# Jlink_OB.net
KiCad netlist of a schematic drawn in Altium Designer
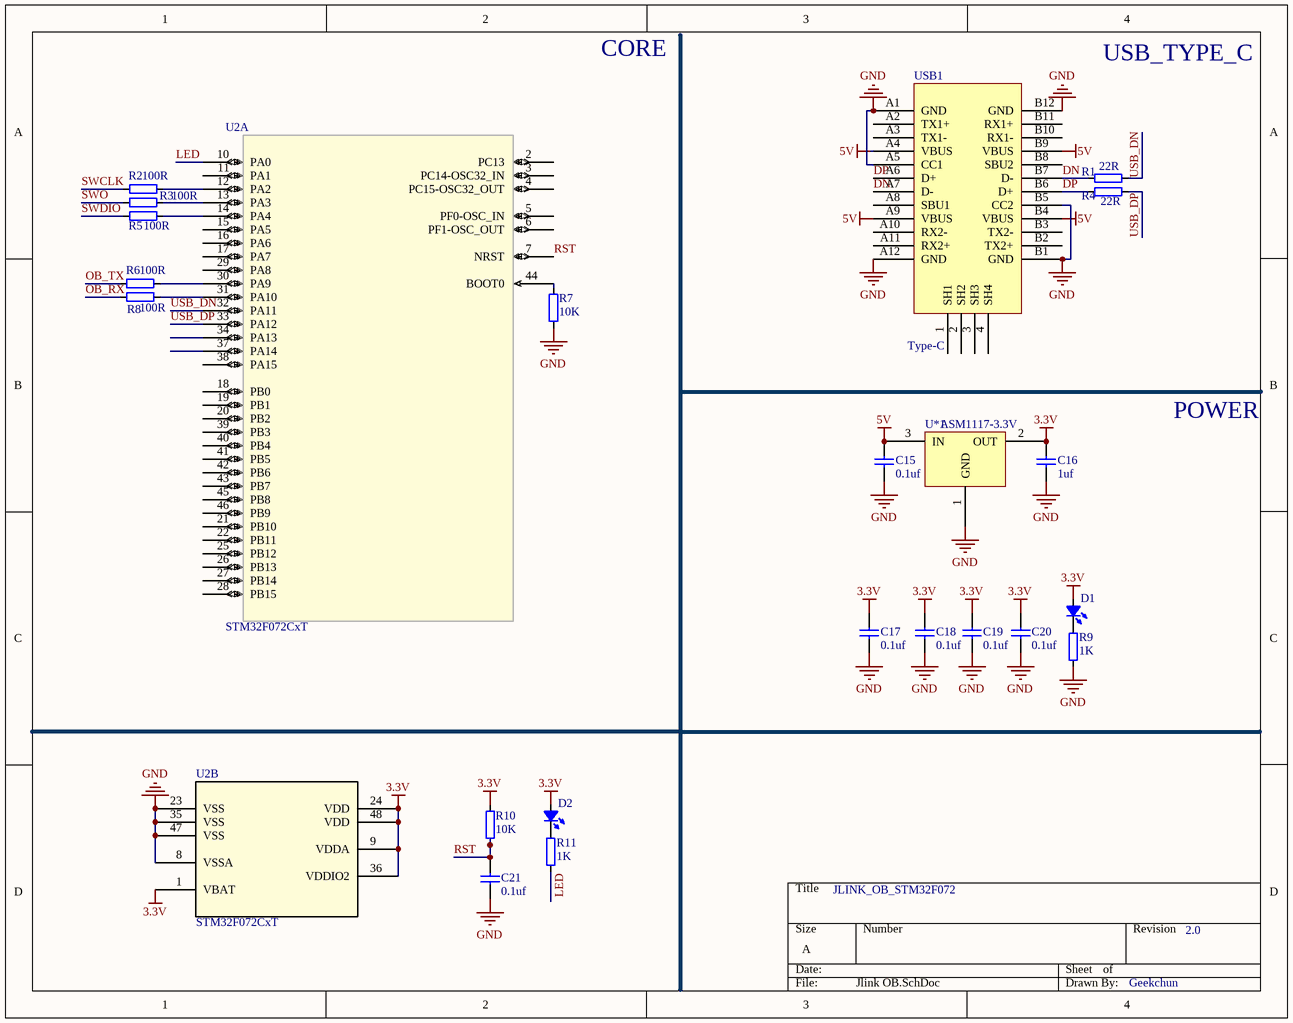
[diagram p0: Jlink OB.SchDoc]

(export (version "E")
  (design (tool "Eeschema 10.0.6"))
  (components
    (comp (ref "C15")
      (value "0.1uf")
      (footprint "C 0603_L")
      (description "Capacitor, NP0, ?.1pF")
      (fields (field (name "PART NUMBER") "C0402-1.2p") (field (name "PUBLISHER") "Nordic Semiconductor"))
      (libsource (lib "52") (part "CAP"))
    )
    (comp (ref "C16")
      (value "1uf")
      (footprint "C 0603_L")
      (description "Capacitor, NP0, ?.1pF")
      (fields (field (name "PART NUMBER") "C0402-1.2p") (field (name "PUBLISHER") "Nordic Semiconductor"))
      (libsource (lib "52") (part "CAP"))
    )
    (comp (ref "C17")
      (value "0.1uf")
      (footprint "C 0603_L")
      (description "Capacitor, NP0, ?.1pF")
      (fields (field (name "PART NUMBER") "C0402-1.2p") (field (name "PUBLISHER") "Nordic Semiconductor"))
      (libsource (lib "52") (part "CAP"))
    )
    (comp (ref "C18")
      (value "0.1uf")
      (footprint "C 0603_L")
      (description "Capacitor, NP0, ?.1pF")
      (fields (field (name "PART NUMBER") "C0402-1.2p") (field (name "PUBLISHER") "Nordic Semiconductor"))
      (libsource (lib "52") (part "CAP"))
    )
    (comp (ref "C19")
      (value "0.1uf")
      (footprint "C 0603_L")
      (description "Capacitor, NP0, ?.1pF")
      (fields (field (name "PART NUMBER") "C0402-1.2p") (field (name "PUBLISHER") "Nordic Semiconductor"))
      (libsource (lib "52") (part "CAP"))
    )
    (comp (ref "C20")
      (value "0.1uf")
      (footprint "C 0603_L")
      (description "Capacitor, NP0, ?.1pF")
      (fields (field (name "PART NUMBER") "C0402-1.2p") (field (name "PUBLISHER") "Nordic Semiconductor"))
      (libsource (lib "52") (part "CAP"))
    )
    (comp (ref "C21")
      (value "0.1uf")
      (footprint "C 0603_L")
      (description "Capacitor, NP0, ?.1pF")
      (fields (field (name "PART NUMBER") "C0402-1.2p") (field (name "PUBLISHER") "Nordic Semiconductor"))
      (libsource (lib "52") (part "CAP"))
    )
    (comp (ref "D1")
      (value "LED_0603")
      (footprint "LED_0603_BLUE")
      (description "LED")
      (libsource (lib "SCH_Active") (part "LED_0603"))
    )
    (comp (ref "D2")
      (value "LED_0603")
      (footprint "LED_0603_GREEN")
      (description "LED")
      (libsource (lib "SCH_Active") (part "LED_0603"))
    )
    (comp (ref "R1") (value "22R") (footprint "R 0603_L") (libsource (lib "电阻") (part "RES")))
    (comp (ref "R2") (value "100R") (footprint "R 0603_L") (libsource (lib "电阻") (part "RES")))
    (comp (ref "R3") (value "100R") (footprint "R 0603_L") (libsource (lib "电阻") (part "RES")))
    (comp (ref "R4") (value "22R") (footprint "R 0603_L") (libsource (lib "电阻") (part "RES")))
    (comp (ref "R5") (value "100R") (footprint "R 0603_L") (libsource (lib "电阻") (part "RES")))
    (comp (ref "R6") (value "100R") (footprint "R 0603_L") (libsource (lib "电阻") (part "RES")))
    (comp (ref "R7") (value "10K") (footprint "R 0603_L") (libsource (lib "电阻") (part "RES")))
    (comp (ref "R8") (value "100R") (footprint "R 0603_L") (libsource (lib "电阻") (part "RES")))
    (comp (ref "R9") (value "1K") (footprint "R 0603_L") (libsource (lib "电阻") (part "RES")))
    (comp (ref "R10") (value "10K") (footprint "R 0603_L") (libsource (lib "电阻") (part "RES")))
    (comp (ref "R11") (value "1K") (footprint "R 0603_L") (libsource (lib "电阻") (part "RES")))
    (comp (ref "U*1")
      (value "ASM1117-3.3V")
      (footprint "SOT-89")
      (description "三端可调或固定电压3.3V")
      (libsource (lib "STM32F103C及ASM1117") (part "ASM1117-3.3V"))
    )
    (comp (ref "U2")
      (value "STM32F072CxT")
      (footprint "LQFP_P0.5_48")
      (description "Imported")
      (fields
        (field (name "MANUFACTURER_PART_NUMBER") "stm32f072cxt")
        (field (name "COPYRIGHT") "Copyright (C) 2016 Accelerated Designs. All rights reserved")
      )
      (libsource (lib "STM32F072CB") (part "STM32F072CxT"))
    )
    (comp (ref "USB1") (value "Type-C") (footprint "PCBComponent_1") (libsource (lib "元件") (part "Type-C")))
  )
  (nets
    (net (code "1") (name "/DN") (class "Default")
      (node (ref "R1") (pin "1") (pinfunction "1_1") (pintype "passive"))
      (node (ref "USB1") (pin "A7") (pinfunction "D-_A7") (pintype "passive"))
      (node (ref "USB1") (pin "B7") (pinfunction "D-_B7") (pintype "passive"))
    )
    (net (code "2") (name "/DP") (class "Default")
      (node (ref "R4") (pin "1") (pinfunction "1_1") (pintype "passive"))
      (node (ref "USB1") (pin "A6") (pinfunction "D+_A6") (pintype "passive"))
      (node (ref "USB1") (pin "B6") (pinfunction "D+_B6") (pintype "passive"))
    )
    (net (code "3") (name "/LED") (class "Default")
      (node (ref "R11") (pin "1") (pinfunction "1_1") (pintype "passive"))
      (node (ref "U2") (pin "10") (pinfunction "PA0_10") (pintype "bidirectional"))
    )
    (net (code "4") (name "/OB_RX") (class "Default")
      (node (ref "R8") (pin "1") (pinfunction "1_1") (pintype "passive"))
    )
    (net (code "5") (name "/OB_TX") (class "Default")
      (node (ref "R6") (pin "1") (pinfunction "1_1") (pintype "passive"))
    )
    (net (code "6") (name "/RST") (class "Default")
      (node (ref "C21") (pin "2") (pinfunction "2_2") (pintype "passive"))
      (node (ref "R10") (pin "1") (pinfunction "1_1") (pintype "passive"))
      (node (ref "U2") (pin "7") (pinfunction "NRST_7") (pintype "bidirectional"))
    )
    (net (code "7") (name "/SWCLK") (class "Default")
      (node (ref "R2") (pin "1") (pinfunction "1_1") (pintype "passive"))
    )
    (net (code "8") (name "/SWDIO") (class "Default")
      (node (ref "R5") (pin "1") (pinfunction "1_1") (pintype "passive"))
    )
    (net (code "9") (name "/SWO") (class "Default")
      (node (ref "R3") (pin "1") (pinfunction "1_1") (pintype "passive"))
    )
    (net (code "10") (name "/USB_DN") (class "Default")
      (node (ref "R1") (pin "2") (pinfunction "2_2") (pintype "passive"))
      (node (ref "U2") (pin "32") (pinfunction "PA11_32") (pintype "bidirectional"))
    )
    (net (code "11") (name "/USB_DP") (class "Default")
      (node (ref "R4") (pin "2") (pinfunction "2_2") (pintype "passive"))
      (node (ref "U2") (pin "33") (pinfunction "PA12_33") (pintype "bidirectional"))
    )
    (net (code "12") (name "3.3V") (class "Default")
      (node (ref "C16") (pin "2") (pinfunction "2_2") (pintype "passive"))
      (node (ref "C17") (pin "2") (pinfunction "2_2") (pintype "passive"))
      (node (ref "C18") (pin "2") (pinfunction "2_2") (pintype "passive"))
      (node (ref "C19") (pin "2") (pinfunction "2_2") (pintype "passive"))
      (node (ref "C20") (pin "2") (pinfunction "2_2") (pintype "passive"))
      (node (ref "D1") (pin "1") (pinfunction "A_1") (pintype "passive"))
      (node (ref "D2") (pin "1") (pinfunction "A_1") (pintype "passive"))
      (node (ref "R10") (pin "2") (pinfunction "2_2") (pintype "passive"))
      (node (ref "U*1") (pin "2") (pinfunction "OUT_2") (pintype "passive"))
      (node (ref "U2") (pin "1") (pinfunction "VBAT_1") (pintype "power_in"))
      (node (ref "U2") (pin "24") (pinfunction "VDD_24") (pintype "power_in"))
      (node (ref "U2") (pin "36") (pinfunction "VDDIO2_36") (pintype "power_in"))
      (node (ref "U2") (pin "48") (pinfunction "VDD_48") (pintype "power_in"))
      (node (ref "U2") (pin "9") (pinfunction "VDDA_9") (pintype "power_in"))
    )
    (net (code "13") (name "5V") (class "Default")
      (node (ref "C15") (pin "2") (pinfunction "2_2") (pintype "passive"))
      (node (ref "U*1") (pin "3") (pinfunction "IN_3") (pintype "passive"))
      (node (ref "USB1") (pin "A4") (pinfunction "VBUS_A4") (pintype "passive"))
      (node (ref "USB1") (pin "A9") (pinfunction "VBUS_A9") (pintype "passive"))
      (node (ref "USB1") (pin "B4") (pinfunction "VBUS_B4") (pintype "passive"))
      (node (ref "USB1") (pin "B9") (pinfunction "VBUS_B9") (pintype "passive"))
    )
    (net (code "14") (name "GND") (class "Default")
      (node (ref "C15") (pin "1") (pinfunction "1_1") (pintype "passive"))
      (node (ref "C16") (pin "1") (pinfunction "1_1") (pintype "passive"))
      (node (ref "C17") (pin "1") (pinfunction "1_1") (pintype "passive"))
      (node (ref "C18") (pin "1") (pinfunction "1_1") (pintype "passive"))
      (node (ref "C19") (pin "1") (pinfunction "1_1") (pintype "passive"))
      (node (ref "C20") (pin "1") (pinfunction "1_1") (pintype "passive"))
      (node (ref "C21") (pin "1") (pinfunction "1_1") (pintype "passive"))
      (node (ref "R7") (pin "2") (pinfunction "2_2") (pintype "passive"))
      (node (ref "R9") (pin "1") (pinfunction "1_1") (pintype "passive"))
      (node (ref "U*1") (pin "1") (pinfunction "GND_1") (pintype "passive"))
      (node (ref "U2") (pin "23") (pinfunction "VSS_23") (pintype "power_in"))
      (node (ref "U2") (pin "35") (pinfunction "VSS_35") (pintype "power_in"))
      (node (ref "U2") (pin "47") (pinfunction "VSS_47") (pintype "power_in"))
      (node (ref "U2") (pin "8") (pinfunction "VSSA_8") (pintype "power_in"))
      (node (ref "USB1") (pin "A1") (pinfunction "GND_A1") (pintype "passive"))
      (node (ref "USB1") (pin "A12") (pinfunction "GND_A12") (pintype "passive"))
      (node (ref "USB1") (pin "A5") (pinfunction "CC1_A5") (pintype "passive"))
      (node (ref "USB1") (pin "B1") (pinfunction "GND_B1") (pintype "passive"))
      (node (ref "USB1") (pin "B12") (pinfunction "GND_B12") (pintype "passive"))
      (node (ref "USB1") (pin "B5") (pinfunction "CC2_B5") (pintype "passive"))
    )
    (net (code "15") (name "Net-(D1-K)") (class "Default")
      (node (ref "D1") (pin "2") (pinfunction "K_2") (pintype "passive"))
      (node (ref "R9") (pin "2") (pinfunction "2_2") (pintype "passive"))
    )
    (net (code "16") (name "Net-(D2-K)") (class "Default")
      (node (ref "D2") (pin "2") (pinfunction "K_2") (pintype "passive"))
      (node (ref "R11") (pin "2") (pinfunction "2_2") (pintype "passive"))
    )
    (net (code "17") (name "Net-(U2A-BOOT0)") (class "Default")
      (node (ref "R7") (pin "1") (pinfunction "1_1") (pintype "passive"))
      (node (ref "U2") (pin "44") (pinfunction "BOOT0_44") (pintype "input"))
    )
    (net (code "18") (name "Net-(U2A-PA2)") (class "Default")
      (node (ref "R2") (pin "2") (pinfunction "2_2") (pintype "passive"))
      (node (ref "U2") (pin "12") (pinfunction "PA2_12") (pintype "bidirectional"))
    )
    (net (code "19") (name "Net-(U2A-PA3)") (class "Default")
      (node (ref "R3") (pin "2") (pinfunction "2_2") (pintype "passive"))
      (node (ref "U2") (pin "13") (pinfunction "PA3_13") (pintype "bidirectional"))
    )
    (net (code "20") (name "Net-(U2A-PA4)") (class "Default")
      (node (ref "R5") (pin "2") (pinfunction "2_2") (pintype "passive"))
      (node (ref "U2") (pin "14") (pinfunction "PA4_14") (pintype "bidirectional"))
    )
    (net (code "21") (name "Net-(U2A-PA9)") (class "Default")
      (node (ref "R6") (pin "2") (pinfunction "2_2") (pintype "passive"))
      (node (ref "U2") (pin "30") (pinfunction "PA9_30") (pintype "bidirectional"))
    )
    (net (code "22") (name "Net-(U2A-PA10)") (class "Default")
      (node (ref "R8") (pin "2") (pinfunction "2_2") (pintype "passive"))
      (node (ref "U2") (pin "31") (pinfunction "PA10_31") (pintype "bidirectional"))
    )
    (net (code "23") (name "unconnected-(U2A-PA1-Pad11)") (class "Default")
      (node (ref "U2") (pin "11") (pinfunction "PA1_11") (pintype "bidirectional"))
    )
    (net (code "24") (name "unconnected-(U2A-PA5-Pad15)") (class "Default")
      (node (ref "U2") (pin "15") (pinfunction "PA5_15") (pintype "bidirectional"))
    )
    (net (code "25") (name "unconnected-(U2A-PA6-Pad16)") (class "Default")
      (node (ref "U2") (pin "16") (pinfunction "PA6_16") (pintype "bidirectional"))
    )
    (net (code "26") (name "unconnected-(U2A-PA7-Pad17)") (class "Default")
      (node (ref "U2") (pin "17") (pinfunction "PA7_17") (pintype "bidirectional"))
    )
    (net (code "27") (name "unconnected-(U2A-PA8-Pad29)") (class "Default")
      (node (ref "U2") (pin "29") (pinfunction "PA8_29") (pintype "bidirectional"))
    )
    (net (code "28") (name "unconnected-(U2A-PA13-Pad34)") (class "Default")
      (node (ref "U2") (pin "34") (pinfunction "PA13_34") (pintype "bidirectional"))
    )
    (net (code "29") (name "unconnected-(U2A-PA14-Pad37)") (class "Default")
      (node (ref "U2") (pin "37") (pinfunction "PA14_37") (pintype "bidirectional"))
    )
    (net (code "30") (name "unconnected-(U2A-PA15-Pad38)") (class "Default")
      (node (ref "U2") (pin "38") (pinfunction "PA15_38") (pintype "bidirectional"))
    )
    (net (code "31") (name "unconnected-(U2A-PB0-Pad18)") (class "Default")
      (node (ref "U2") (pin "18") (pinfunction "PB0_18") (pintype "bidirectional"))
    )
    (net (code "32") (name "unconnected-(U2A-PB1-Pad19)") (class "Default")
      (node (ref "U2") (pin "19") (pinfunction "PB1_19") (pintype "bidirectional"))
    )
    (net (code "33") (name "unconnected-(U2A-PB2-Pad20)") (class "Default")
      (node (ref "U2") (pin "20") (pinfunction "PB2_20") (pintype "bidirectional"))
    )
    (net (code "34") (name "unconnected-(U2A-PB3-Pad39)") (class "Default")
      (node (ref "U2") (pin "39") (pinfunction "PB3_39") (pintype "bidirectional"))
    )
    (net (code "35") (name "unconnected-(U2A-PB4-Pad40)") (class "Default")
      (node (ref "U2") (pin "40") (pinfunction "PB4_40") (pintype "bidirectional"))
    )
    (net (code "36") (name "unconnected-(U2A-PB5-Pad41)") (class "Default")
      (node (ref "U2") (pin "41") (pinfunction "PB5_41") (pintype "bidirectional"))
    )
    (net (code "37") (name "unconnected-(U2A-PB6-Pad42)") (class "Default")
      (node (ref "U2") (pin "42") (pinfunction "PB6_42") (pintype "bidirectional"))
    )
    (net (code "38") (name "unconnected-(U2A-PB7-Pad43)") (class "Default")
      (node (ref "U2") (pin "43") (pinfunction "PB7_43") (pintype "bidirectional"))
    )
    (net (code "39") (name "unconnected-(U2A-PB8-Pad45)") (class "Default")
      (node (ref "U2") (pin "45") (pinfunction "PB8_45") (pintype "bidirectional"))
    )
    (net (code "40") (name "unconnected-(U2A-PB9-Pad46)") (class "Default")
      (node (ref "U2") (pin "46") (pinfunction "PB9_46") (pintype "bidirectional"))
    )
    (net (code "41") (name "unconnected-(U2A-PB10-Pad21)") (class "Default")
      (node (ref "U2") (pin "21") (pinfunction "PB10_21") (pintype "bidirectional"))
    )
    (net (code "42") (name "unconnected-(U2A-PB11-Pad22)") (class "Default")
      (node (ref "U2") (pin "22") (pinfunction "PB11_22") (pintype "bidirectional"))
    )
    (net (code "43") (name "unconnected-(U2A-PB12-Pad25)") (class "Default")
      (node (ref "U2") (pin "25") (pinfunction "PB12_25") (pintype "bidirectional"))
    )
    (net (code "44") (name "unconnected-(U2A-PB13-Pad26)") (class "Default")
      (node (ref "U2") (pin "26") (pinfunction "PB13_26") (pintype "bidirectional"))
    )
    (net (code "45") (name "unconnected-(U2A-PB14-Pad27)") (class "Default")
      (node (ref "U2") (pin "27") (pinfunction "PB14_27") (pintype "bidirectional"))
    )
    (net (code "46") (name "unconnected-(U2A-PB15-Pad28)") (class "Default")
      (node (ref "U2") (pin "28") (pinfunction "PB15_28") (pintype "bidirectional"))
    )
    (net (code "47") (name "unconnected-(U2A-PC13-Pad2)") (class "Default")
      (node (ref "U2") (pin "2") (pinfunction "PC13_2") (pintype "bidirectional"))
    )
    (net (code "48") (name "unconnected-(U2A-PC14-OSC32_IN-Pad3)") (class "Default")
      (node (ref "U2") (pin "3") (pinfunction "PC14-OSC32_IN_3") (pintype "bidirectional"))
    )
    (net (code "49") (name "unconnected-(U2A-PC15-OSC32_OUT-Pad4)") (class "Default")
      (node (ref "U2") (pin "4") (pinfunction "PC15-OSC32_OUT_4") (pintype "bidirectional"))
    )
    (net (code "50") (name "unconnected-(U2A-PF0-OSC_IN-Pad5)") (class "Default")
      (node (ref "U2") (pin "5") (pinfunction "PF0-OSC_IN_5") (pintype "bidirectional"))
    )
    (net (code "51") (name "unconnected-(U2A-PF1-OSC_OUT-Pad6)") (class "Default")
      (node (ref "U2") (pin "6") (pinfunction "PF1-OSC_OUT_6") (pintype "bidirectional"))
    )
    (net (code "52") (name "unconnected-(USB1-RX1+-PadB11)") (class "Default")
      (node (ref "USB1") (pin "B11") (pinfunction "RX1+_B11") (pintype "passive"))
    )
    (net (code "53") (name "unconnected-(USB1-RX1--PadB10)") (class "Default")
      (node (ref "USB1") (pin "B10") (pinfunction "RX1-_B10") (pintype "passive"))
    )
    (net (code "54") (name "unconnected-(USB1-RX2+-PadA11)") (class "Default")
      (node (ref "USB1") (pin "A11") (pinfunction "RX2+_A11") (pintype "passive"))
    )
    (net (code "55") (name "unconnected-(USB1-RX2--PadA10)") (class "Default")
      (node (ref "USB1") (pin "A10") (pinfunction "RX2-_A10") (pintype "passive"))
    )
    (net (code "56") (name "unconnected-(USB1-SBU1-PadA8)") (class "Default")
      (node (ref "USB1") (pin "A8") (pinfunction "SBU1_A8") (pintype "passive"))
    )
    (net (code "57") (name "unconnected-(USB1-SBU2-PadB8)") (class "Default")
      (node (ref "USB1") (pin "B8") (pinfunction "SBU2_B8") (pintype "passive"))
    )
    (net (code "58") (name "unconnected-(USB1-SH1-Pad1)") (class "Default")
      (node (ref "USB1") (pin "1") (pinfunction "SH1_1") (pintype "passive"))
    )
    (net (code "59") (name "unconnected-(USB1-SH2-Pad2)") (class "Default")
      (node (ref "USB1") (pin "2") (pinfunction "SH2_2") (pintype "passive"))
    )
    (net (code "60") (name "unconnected-(USB1-SH3-Pad3)") (class "Default")
      (node (ref "USB1") (pin "3") (pinfunction "SH3_3") (pintype "passive"))
    )
    (net (code "61") (name "unconnected-(USB1-SH4-Pad4)") (class "Default")
      (node (ref "USB1") (pin "4") (pinfunction "SH4_4") (pintype "passive"))
    )
    (net (code "62") (name "unconnected-(USB1-TX1+-PadA2)") (class "Default")
      (node (ref "USB1") (pin "A2") (pinfunction "TX1+_A2") (pintype "passive"))
    )
    (net (code "63") (name "unconnected-(USB1-TX1--PadA3)") (class "Default")
      (node (ref "USB1") (pin "A3") (pinfunction "TX1-_A3") (pintype "passive"))
    )
    (net (code "64") (name "unconnected-(USB1-TX2+-PadB2)") (class "Default")
      (node (ref "USB1") (pin "B2") (pinfunction "TX2+_B2") (pintype "passive"))
    )
    (net (code "65") (name "unconnected-(USB1-TX2--PadB3)") (class "Default")
      (node (ref "USB1") (pin "B3") (pinfunction "TX2-_B3") (pintype "passive"))
    )
  )
)
